# untitled.net
KiCad netlist of a schematic drawn in EAGLE
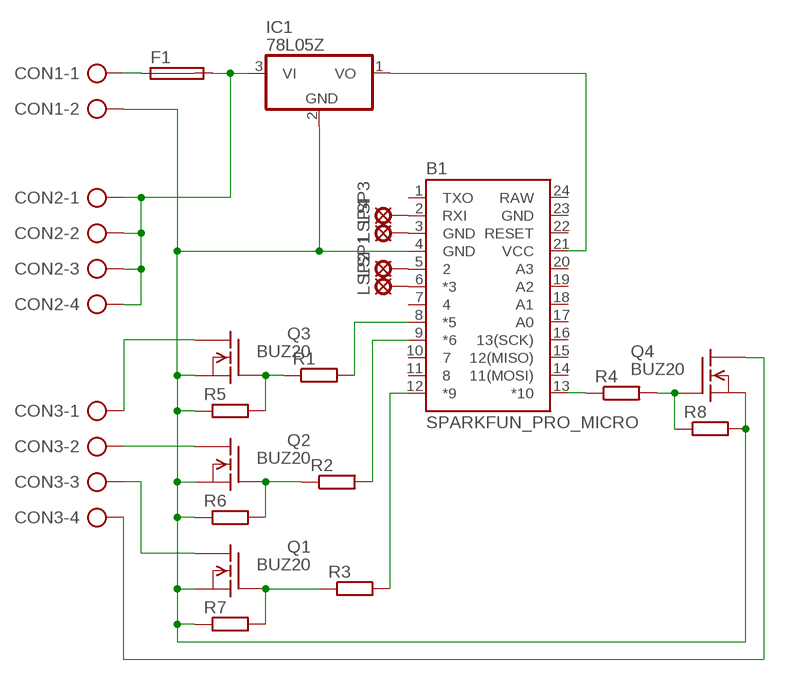
[diagram p0: schematic, sheet 1]

(export (version "E")
  (design (tool "Eeschema 10.0.6"))
  (components
    (comp (ref "B1")
      (value "SPARKFUN_PRO_MICRO")
      (footprint "eagle-import:SPARKFUN_PRO_MICRO")
      (libsource (lib "eagle-import") (part "SPARKFUN_PRO_MICRO"))
    )
    (comp (ref "CON1")
      (value "AK500/2")
      (footprint "eagle-import:AK500_2")
      (libsource (lib "eagle-import") (part "AK500/2"))
    )
    (comp (ref "CON2")
      (value "AK500/4")
      (footprint "eagle-import:AK500_4")
      (libsource (lib "eagle-import") (part "AK500/4"))
    )
    (comp (ref "CON3")
      (value "AK500/4")
      (footprint "eagle-import:AK500_4")
      (libsource (lib "eagle-import") (part "AK500/4"))
    )
    (comp (ref "F1")
      (value "SH25")
      (footprint "eagle-import:SH25")
      (fields (field (name "MF") "SCHURTER") (field (name "MPN") "0031.8211"))
      (libsource (lib "eagle-import") (part "SH25"))
    )
    (comp (ref "IC1")
      (value "78L05Z")
      (footprint "eagle-import:TO92")
      (libsource (lib "eagle-import") (part "78ZL05"))
    )
    (comp (ref "LSP1")
      (value "LSP10")
      (footprint "eagle-import:LSP10")
      (libsource (lib "eagle-import") (part "LSP10"))
    )
    (comp (ref "LSP2")
      (value "LSP10")
      (footprint "eagle-import:LSP10")
      (libsource (lib "eagle-import") (part "LSP10"))
    )
    (comp (ref "LSP3")
      (value "LSP10")
      (footprint "eagle-import:LSP10")
      (libsource (lib "eagle-import") (part "LSP10"))
    )
    (comp (ref "LSP4")
      (value "LSP10")
      (footprint "eagle-import:LSP10")
      (libsource (lib "eagle-import") (part "LSP10"))
    )
    (comp (ref "Q1")
      (value "BUZ20")
      (footprint "eagle-import:TO220")
      (libsource (lib "eagle-import") (part "BUZ20"))
    )
    (comp (ref "Q2")
      (value "BUZ20")
      (footprint "eagle-import:TO220")
      (libsource (lib "eagle-import") (part "BUZ20"))
    )
    (comp (ref "Q3")
      (value "BUZ20")
      (footprint "eagle-import:TO220")
      (libsource (lib "eagle-import") (part "BUZ20"))
    )
    (comp (ref "Q4")
      (value "BUZ20")
      (footprint "eagle-import:TO220")
      (libsource (lib "eagle-import") (part "BUZ20"))
    )
    (comp (ref "R1")
      (value "R-EU_0207/10")
      (footprint "eagle-import:0207_10")
      (libsource (lib "eagle-import") (part "R-EU_0207/10"))
    )
    (comp (ref "R2")
      (value "R-EU_0207/10")
      (footprint "eagle-import:0207_10")
      (libsource (lib "eagle-import") (part "R-EU_0207/10"))
    )
    (comp (ref "R3")
      (value "R-EU_0207/10")
      (footprint "eagle-import:0207_10")
      (libsource (lib "eagle-import") (part "R-EU_0207/10"))
    )
    (comp (ref "R4")
      (value "R-EU_0207/10")
      (footprint "eagle-import:0207_10")
      (libsource (lib "eagle-import") (part "R-EU_0207/10"))
    )
    (comp (ref "R5")
      (value "R-EU_0207/10")
      (footprint "eagle-import:0207_10")
      (libsource (lib "eagle-import") (part "R-EU_0207/10"))
    )
    (comp (ref "R6")
      (value "R-EU_0207/10")
      (footprint "eagle-import:0207_10")
      (libsource (lib "eagle-import") (part "R-EU_0207/10"))
    )
    (comp (ref "R7")
      (value "R-EU_0207/10")
      (footprint "eagle-import:0207_10")
      (libsource (lib "eagle-import") (part "R-EU_0207/10"))
    )
    (comp (ref "R8")
      (value "R-EU_0207/10")
      (footprint "eagle-import:0207_10")
      (libsource (lib "eagle-import") (part "R-EU_0207/10"))
    )
  )
  (nets
    (net (code "1") (name "/GND") (class "Default")
      (node (ref "B1") (pin "23") (pinfunction "GND_23") (pintype "power_in"))
    )
    (net (code "2") (name "/RAW") (class "Default")
      (node (ref "B1") (pin "24") (pinfunction "RAW_24") (pintype "power_in"))
    )
    (net (code "3") (name "Net-(B1-*3)") (class "Default")
      (node (ref "B1") (pin "6") (pinfunction "*3_6") (pintype "bidirectional"))
      (node (ref "LSP2") (pin "MP") (pinfunction "MP_MP") (pintype "passive"))
    )
    (net (code "4") (name "Net-(B1-*5)") (class "Default")
      (node (ref "B1") (pin "8") (pinfunction "*5_8") (pintype "bidirectional"))
      (node (ref "R1") (pin "2") (pinfunction "2_2") (pintype "passive"))
    )
    (net (code "5") (name "Net-(B1-*6)") (class "Default")
      (node (ref "B1") (pin "9") (pinfunction "*6_9") (pintype "bidirectional"))
      (node (ref "R2") (pin "2") (pinfunction "2_2") (pintype "passive"))
    )
    (net (code "6") (name "Net-(B1-*9)") (class "Default")
      (node (ref "B1") (pin "12") (pinfunction "*9_12") (pintype "bidirectional"))
      (node (ref "R3") (pin "2") (pinfunction "2_2") (pintype "passive"))
    )
    (net (code "7") (name "Net-(B1-*10)") (class "Default")
      (node (ref "B1") (pin "13") (pinfunction "*10_13") (pintype "bidirectional"))
      (node (ref "R4") (pin "1") (pinfunction "1_1") (pintype "passive"))
    )
    (net (code "8") (name "Net-(B1-2)") (class "Default")
      (node (ref "B1") (pin "5") (pinfunction "2_5") (pintype "bidirectional"))
      (node (ref "LSP1") (pin "MP") (pinfunction "MP_MP") (pintype "passive"))
    )
    (net (code "9") (name "Net-(B1-GND-Pad3)") (class "Default")
      (node (ref "B1") (pin "3") (pinfunction "GND_3") (pintype "power_in"))
      (node (ref "LSP4") (pin "MP") (pinfunction "MP_MP") (pintype "passive"))
    )
    (net (code "10") (name "Net-(B1-RXI)") (class "Default")
      (node (ref "B1") (pin "2") (pinfunction "RXI_2") (pintype "bidirectional"))
      (node (ref "LSP3") (pin "MP") (pinfunction "MP_MP") (pintype "passive"))
    )
    (net (code "11") (name "Net-(B1-VCC)") (class "Default")
      (node (ref "B1") (pin "21") (pinfunction "VCC_21") (pintype "power_in"))
      (node (ref "IC1") (pin "1") (pinfunction "VO_1") (pintype "passive"))
    )
    (net (code "12") (name "Net-(CON1A-KL)") (class "Default")
      (node (ref "CON1") (pin "1") (pinfunction "KL_1") (pintype "passive"))
      (node (ref "F1") (pin "1") (pinfunction "1_1") (pintype "passive"))
    )
    (net (code "13") (name "Net-(CON1B-KL)") (class "Default")
      (node (ref "B1") (pin "4") (pinfunction "GND_4") (pintype "power_in"))
      (node (ref "CON1") (pin "2") (pinfunction "KL_2") (pintype "passive"))
      (node (ref "IC1") (pin "2") (pinfunction "GND_2") (pintype "passive"))
      (node (ref "Q1") (pin "3") (pinfunction "S_3") (pintype "passive"))
      (node (ref "Q2") (pin "3") (pinfunction "S_3") (pintype "passive"))
      (node (ref "Q3") (pin "3") (pinfunction "S_3") (pintype "passive"))
      (node (ref "Q4") (pin "3") (pinfunction "S_3") (pintype "passive"))
      (node (ref "R5") (pin "1") (pinfunction "1_1") (pintype "passive"))
      (node (ref "R6") (pin "1") (pinfunction "1_1") (pintype "passive"))
      (node (ref "R7") (pin "1") (pinfunction "1_1") (pintype "passive"))
      (node (ref "R8") (pin "2") (pinfunction "2_2") (pintype "passive"))
    )
    (net (code "14") (name "Net-(CON2A-KL)") (class "Default")
      (node (ref "CON2") (pin "1") (pinfunction "KL_1") (pintype "passive"))
      (node (ref "CON2") (pin "2") (pinfunction "KL_2") (pintype "passive"))
      (node (ref "CON2") (pin "3") (pinfunction "KL_3") (pintype "passive"))
      (node (ref "CON2") (pin "4") (pinfunction "KL_4") (pintype "passive"))
      (node (ref "F1") (pin "2") (pinfunction "2_2") (pintype "passive"))
      (node (ref "IC1") (pin "3") (pinfunction "VI_3") (pintype "input"))
    )
    (net (code "15") (name "Net-(CON3A-KL)") (class "Default")
      (node (ref "CON3") (pin "1") (pinfunction "KL_1") (pintype "passive"))
      (node (ref "Q3") (pin "2") (pinfunction "D_2") (pintype "passive"))
    )
    (net (code "16") (name "Net-(CON3B-KL)") (class "Default")
      (node (ref "CON3") (pin "2") (pinfunction "KL_2") (pintype "passive"))
      (node (ref "Q2") (pin "2") (pinfunction "D_2") (pintype "passive"))
    )
    (net (code "17") (name "Net-(CON3C-KL)") (class "Default")
      (node (ref "CON3") (pin "3") (pinfunction "KL_3") (pintype "passive"))
      (node (ref "Q1") (pin "2") (pinfunction "D_2") (pintype "passive"))
    )
    (net (code "18") (name "Net-(CON3D-KL)") (class "Default")
      (node (ref "CON3") (pin "4") (pinfunction "KL_4") (pintype "passive"))
      (node (ref "Q4") (pin "2") (pinfunction "D_2") (pintype "passive"))
    )
    (net (code "19") (name "Net-(Q1-G)") (class "Default")
      (node (ref "Q1") (pin "1") (pinfunction "G_1") (pintype "passive"))
      (node (ref "R3") (pin "1") (pinfunction "1_1") (pintype "passive"))
      (node (ref "R7") (pin "2") (pinfunction "2_2") (pintype "passive"))
    )
    (net (code "20") (name "Net-(Q2-G)") (class "Default")
      (node (ref "Q2") (pin "1") (pinfunction "G_1") (pintype "passive"))
      (node (ref "R2") (pin "1") (pinfunction "1_1") (pintype "passive"))
      (node (ref "R6") (pin "2") (pinfunction "2_2") (pintype "passive"))
    )
    (net (code "21") (name "Net-(Q3-G)") (class "Default")
      (node (ref "Q3") (pin "1") (pinfunction "G_1") (pintype "passive"))
      (node (ref "R1") (pin "1") (pinfunction "1_1") (pintype "passive"))
      (node (ref "R5") (pin "2") (pinfunction "2_2") (pintype "passive"))
    )
    (net (code "22") (name "Net-(Q4-G)") (class "Default")
      (node (ref "Q4") (pin "1") (pinfunction "G_1") (pintype "passive"))
      (node (ref "R4") (pin "2") (pinfunction "2_2") (pintype "passive"))
      (node (ref "R8") (pin "1") (pinfunction "1_1") (pintype "passive"))
    )
    (net (code "23") (name "unconnected-(B1-4-Pad7)") (class "Default")
      (node (ref "B1") (pin "7") (pinfunction "4_7") (pintype "bidirectional"))
    )
    (net (code "24") (name "unconnected-(B1-7-Pad10)") (class "Default")
      (node (ref "B1") (pin "10") (pinfunction "7_10") (pintype "bidirectional"))
    )
    (net (code "25") (name "unconnected-(B1-8-Pad11)") (class "Default")
      (node (ref "B1") (pin "11") (pinfunction "8_11") (pintype "bidirectional"))
    )
    (net (code "26") (name "unconnected-(B1-11(MOSI)-Pad14)") (class "Default")
      (node (ref "B1") (pin "14") (pinfunction "11(MOSI)_14") (pintype "bidirectional"))
    )
    (net (code "27") (name "unconnected-(B1-12(MISO)-Pad15)") (class "Default")
      (node (ref "B1") (pin "15") (pinfunction "12(MISO)_15") (pintype "bidirectional"))
    )
    (net (code "28") (name "unconnected-(B1-13(SCK)-Pad16)") (class "Default")
      (node (ref "B1") (pin "16") (pinfunction "13(SCK)_16") (pintype "bidirectional"))
    )
    (net (code "29") (name "unconnected-(B1-A0-Pad17)") (class "Default")
      (node (ref "B1") (pin "17") (pinfunction "A0_17") (pintype "bidirectional"))
    )
    (net (code "30") (name "unconnected-(B1-A1-Pad18)") (class "Default")
      (node (ref "B1") (pin "18") (pinfunction "A1_18") (pintype "bidirectional"))
    )
    (net (code "31") (name "unconnected-(B1-A2-Pad19)") (class "Default")
      (node (ref "B1") (pin "19") (pinfunction "A2_19") (pintype "bidirectional"))
    )
    (net (code "32") (name "unconnected-(B1-A3-Pad20)") (class "Default")
      (node (ref "B1") (pin "20") (pinfunction "A3_20") (pintype "bidirectional"))
    )
    (net (code "33") (name "unconnected-(B1-RESET-Pad22)") (class "Default")
      (node (ref "B1") (pin "22") (pinfunction "RESET_22") (pintype "bidirectional"))
    )
    (net (code "34") (name "unconnected-(B1-TXO-Pad1)") (class "Default")
      (node (ref "B1") (pin "1") (pinfunction "TXO_1") (pintype "bidirectional"))
    )
  )
)
